# stepup-uc3845.net
KiCad netlist of a schematic drawn in EAGLE
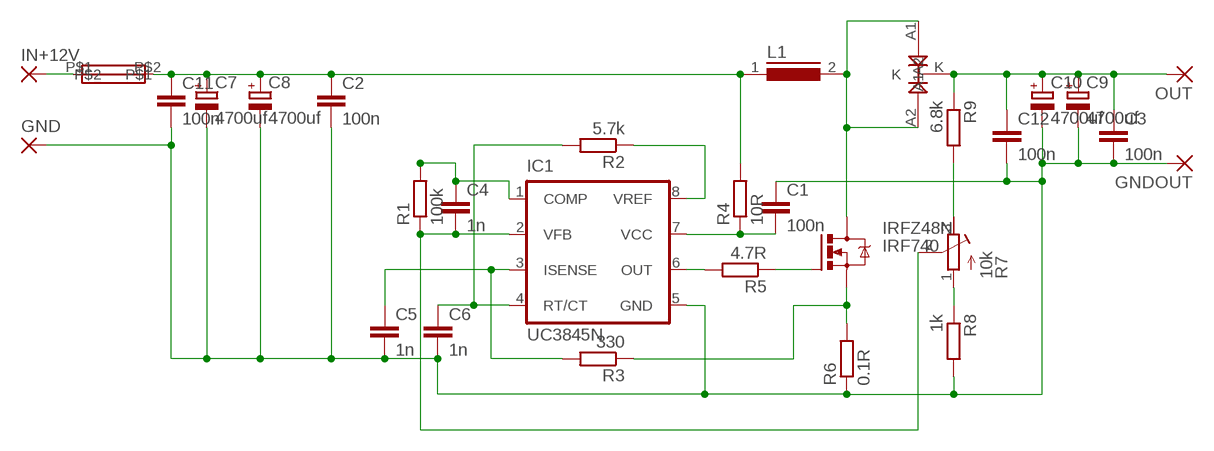
[diagram p0: schematic, sheet 1]

(export (version "E")
  (design (tool "Eeschema 10.0.6"))
  (components
    (comp (ref "C1")
      (value "100n")
      (footprint "eagle-import:C050-025X075")
      (libsource (lib "eagle-import") (part "C-EU050-025X075"))
    )
    (comp (ref "C2")
      (value "100n")
      (footprint "eagle-import:C050-025X075")
      (libsource (lib "eagle-import") (part "C-EU050-025X075"))
    )
    (comp (ref "C3")
      (value "100n")
      (footprint "eagle-import:C050-025X075")
      (libsource (lib "eagle-import") (part "C-EU050-025X075"))
    )
    (comp (ref "C4")
      (value "1n")
      (footprint "eagle-import:C050-025X075")
      (libsource (lib "eagle-import") (part "C-EU050-025X075"))
    )
    (comp (ref "C5")
      (value "1n")
      (footprint "eagle-import:C050-025X075")
      (libsource (lib "eagle-import") (part "C-EU050-025X075"))
    )
    (comp (ref "C6")
      (value "1n")
      (footprint "eagle-import:C050-025X075")
      (libsource (lib "eagle-import") (part "C-EU050-025X075"))
    )
    (comp (ref "C7")
      (value "4700uf")
      (footprint "eagle-import:E7,5-16")
      (libsource (lib "eagle-import") (part "CPOL-EUE7.5-16"))
    )
    (comp (ref "C8")
      (value "4700uf")
      (footprint "eagle-import:E7,5-16")
      (libsource (lib "eagle-import") (part "CPOL-EUE7.5-16"))
    )
    (comp (ref "C9")
      (value "4700uf")
      (footprint "eagle-import:E7,5-18")
      (libsource (lib "eagle-import") (part "CPOL-EUE7.5-18"))
    )
    (comp (ref "C10")
      (value "4700uf")
      (footprint "eagle-import:E7,5-18")
      (libsource (lib "eagle-import") (part "CPOL-EUE7.5-18"))
    )
    (comp (ref "C11")
      (value "100n")
      (footprint "eagle-import:C050-025X075")
      (libsource (lib "eagle-import") (part "C-EU050-025X075"))
    )
    (comp (ref "C12")
      (value "100n")
      (footprint "eagle-import:C050-025X075")
      (libsource (lib "eagle-import") (part "C-EU050-025X075"))
    )
    (comp (ref "F1")
      (value "10A")
      (footprint "eagle-import:FUSE38X12")
      (libsource (lib "eagle-import") (part "FUSE38X12"))
    )
    (comp (ref "GND")
      (value "3,81/1,1")
      (footprint "eagle-import:3,81_1,1")
      (libsource (lib "eagle-import") (part "3,81/1,1"))
    )
    (comp (ref "GNDOUT")
      (value "3,81/1,1")
      (footprint "eagle-import:3,81_1,1")
      (libsource (lib "eagle-import") (part "3,81/1,1"))
    )
    (comp (ref "IC1")
      (value "UC3845N")
      (footprint "eagle-import:DIL08")
      (libsource (lib "eagle-import") (part "UC384N5"))
    )
    (comp (ref "IN+12V")
      (value "3,81/1,1")
      (footprint "eagle-import:3,81_1,1")
      (libsource (lib "eagle-import") (part "3,81/1,1"))
    )
    (comp (ref "IRFZ48N")
      (value "IRF740")
      (footprint "eagle-import:TO220BV")
      (libsource (lib "eagle-import") (part "IRF740"))
    )
    (comp (ref "L1")
      (value "R3311D11")
      (footprint "eagle-import:11-33")
      (libsource (lib "eagle-import") (part "R3311D11"))
    )
    (comp (ref "OUT")
      (value "3,81/1,1")
      (footprint "eagle-import:3,81_1,1")
      (libsource (lib "eagle-import") (part "3,81/1,1"))
    )
    (comp (ref "R1")
      (value "100k")
      (footprint "eagle-import:0204_7")
      (libsource (lib "eagle-import") (part "resistor_348_R-EU_0204/7"))
    )
    (comp (ref "R2")
      (value "5.7k")
      (footprint "eagle-import:0207_7")
      (libsource (lib "eagle-import") (part "R-EU_0207/7"))
    )
    (comp (ref "R3")
      (value "330")
      (footprint "eagle-import:0207_7")
      (libsource (lib "eagle-import") (part "R-EU_0207/7"))
    )
    (comp (ref "R4")
      (value "10R")
      (footprint "eagle-import:0617_17")
      (libsource (lib "eagle-import") (part "resistor_348_R-EU_0617/17"))
    )
    (comp (ref "R5")
      (value "4.7R")
      (footprint "eagle-import:0207_7")
      (libsource (lib "eagle-import") (part "R-EU_0207/7"))
    )
    (comp (ref "R6")
      (value "0.1R")
      (footprint "eagle-import:0922_22")
      (libsource (lib "eagle-import") (part "resistor_348_R-EU_0922/22"))
    )
    (comp (ref "R7")
      (value "10k")
      (footprint "eagle-import:RTRIM3296W")
      (libsource (lib "eagle-import") (part "R-TRIMM3296W"))
    )
    (comp (ref "R8")
      (value "1k")
      (footprint "eagle-import:0207_7")
      (libsource (lib "eagle-import") (part "R-EU_0207/7"))
    )
    (comp (ref "R9")
      (value "6.8k")
      (footprint "eagle-import:0207_7")
      (libsource (lib "eagle-import") (part "R-EU_0207/7"))
    )
    (comp (ref "U$1")
      (value "TO-247-SHOTTKY-K")
      (footprint "eagle-import:TO-247")
      (libsource (lib "eagle-import") (part "TO-247-SHOTTKY-K"))
    )
  )
  (nets
    (net (code "1") (name "Net-(C11-Pad1)") (class "Default")
      (node (ref "C11") (pin "1") (pinfunction "1_1") (pintype "passive"))
      (node (ref "C2") (pin "1") (pinfunction "1_1") (pintype "passive"))
      (node (ref "C7") (pin "+") (pinfunction "+_+") (pintype "passive"))
      (node (ref "C8") (pin "+") (pinfunction "+_+") (pintype "passive"))
      (node (ref "F1") (pin "P$2") (pinfunction "P$2_P$2") (pintype "bidirectional"))
      (node (ref "L1") (pin "1") (pinfunction "1_1") (pintype "passive"))
      (node (ref "R4") (pin "2") (pinfunction "2_2") (pintype "passive"))
    )
    (net (code "2") (name "Net-(GND-P)") (class "Default")
      (node (ref "C1") (pin "1") (pinfunction "1_1") (pintype "passive"))
      (node (ref "C10") (pin "-") (pinfunction "-_-") (pintype "passive"))
      (node (ref "C11") (pin "2") (pinfunction "2_2") (pintype "passive"))
      (node (ref "C12") (pin "2") (pinfunction "2_2") (pintype "passive"))
      (node (ref "C2") (pin "2") (pinfunction "2_2") (pintype "passive"))
      (node (ref "C3") (pin "2") (pinfunction "2_2") (pintype "passive"))
      (node (ref "C5") (pin "2") (pinfunction "2_2") (pintype "passive"))
      (node (ref "C6") (pin "2") (pinfunction "2_2") (pintype "passive"))
      (node (ref "C7") (pin "-") (pinfunction "-_-") (pintype "passive"))
      (node (ref "C8") (pin "-") (pinfunction "-_-") (pintype "passive"))
      (node (ref "C9") (pin "-") (pinfunction "-_-") (pintype "passive"))
      (node (ref "GND") (pin "1") (pinfunction "P_1") (pintype "passive"))
      (node (ref "GNDOUT") (pin "1") (pinfunction "P_1") (pintype "passive"))
      (node (ref "IC1") (pin "5") (pinfunction "GND_5") (pintype "power_in"))
      (node (ref "R6") (pin "1") (pinfunction "1_1") (pintype "passive"))
      (node (ref "R8") (pin "2") (pinfunction "2_2") (pintype "passive"))
    )
    (net (code "3") (name "Net-(IC1-COMP)") (class "Default")
      (node (ref "C4") (pin "1") (pinfunction "1_1") (pintype "passive"))
      (node (ref "IC1") (pin "1") (pinfunction "COMP_1") (pintype "passive"))
      (node (ref "R1") (pin "2") (pinfunction "2_2") (pintype "passive"))
    )
    (net (code "4") (name "Net-(IC1-ISENSE)") (class "Default")
      (node (ref "C5") (pin "1") (pinfunction "1_1") (pintype "passive"))
      (node (ref "IC1") (pin "3") (pinfunction "ISENSE_3") (pintype "input"))
      (node (ref "R3") (pin "2") (pinfunction "2_2") (pintype "passive"))
    )
    (net (code "5") (name "Net-(IC1-OUT)") (class "Default")
      (node (ref "IC1") (pin "6") (pinfunction "OUT_6") (pintype "output"))
      (node (ref "R5") (pin "2") (pinfunction "2_2") (pintype "passive"))
    )
    (net (code "6") (name "Net-(IC1-RT{slash}CT)") (class "Default")
      (node (ref "C6") (pin "1") (pinfunction "1_1") (pintype "passive"))
      (node (ref "IC1") (pin "4") (pinfunction "RT/CT_4") (pintype "passive"))
      (node (ref "R2") (pin "2") (pinfunction "2_2") (pintype "passive"))
    )
    (net (code "7") (name "Net-(IC1-VCC)") (class "Default")
      (node (ref "C1") (pin "2") (pinfunction "2_2") (pintype "passive"))
      (node (ref "IC1") (pin "7") (pinfunction "VCC_7") (pintype "power_in"))
      (node (ref "R4") (pin "1") (pinfunction "1_1") (pintype "passive"))
    )
    (net (code "8") (name "Net-(IC1-VFB)") (class "Default")
      (node (ref "C4") (pin "2") (pinfunction "2_2") (pintype "passive"))
      (node (ref "IC1") (pin "2") (pinfunction "VFB_2") (pintype "input"))
      (node (ref "R1") (pin "1") (pinfunction "1_1") (pintype "passive"))
      (node (ref "R7") (pin "2") (pinfunction "S_2") (pintype "passive"))
    )
    (net (code "9") (name "Net-(IC1-VREF)") (class "Default")
      (node (ref "IC1") (pin "8") (pinfunction "VREF_8") (pintype "passive"))
      (node (ref "R2") (pin "1") (pinfunction "1_1") (pintype "passive"))
    )
    (net (code "10") (name "Net-(IN+12V-P)") (class "Default")
      (node (ref "F1") (pin "P$1") (pinfunction "P$1_P$1") (pintype "bidirectional"))
      (node (ref "IN+12V") (pin "1") (pinfunction "P_1") (pintype "passive"))
    )
    (net (code "11") (name "Net-(IRFZ48N-PadD)") (class "Default")
      (node (ref "IRFZ48N") (pin "D") (pinfunction "D_D") (pintype "passive"))
      (node (ref "L1") (pin "2") (pinfunction "2_2") (pintype "passive"))
      (node (ref "U$1") (pin "A1") (pinfunction "A1_A1") (pintype "bidirectional"))
      (node (ref "U$1") (pin "A2") (pinfunction "A2_A2") (pintype "bidirectional"))
    )
    (net (code "12") (name "Net-(IRFZ48N-PadG)") (class "Default")
      (node (ref "IRFZ48N") (pin "G") (pinfunction "G_G") (pintype "passive"))
      (node (ref "R5") (pin "1") (pinfunction "1_1") (pintype "passive"))
    )
    (net (code "13") (name "Net-(IRFZ48N-PadS)") (class "Default")
      (node (ref "IRFZ48N") (pin "S") (pinfunction "S_S") (pintype "passive"))
      (node (ref "R3") (pin "1") (pinfunction "1_1") (pintype "passive"))
      (node (ref "R6") (pin "2") (pinfunction "2_2") (pintype "passive"))
    )
    (net (code "14") (name "Net-(OUT-P)") (class "Default")
      (node (ref "C10") (pin "+") (pinfunction "+_+") (pintype "passive"))
      (node (ref "C12") (pin "1") (pinfunction "1_1") (pintype "passive"))
      (node (ref "C3") (pin "1") (pinfunction "1_1") (pintype "passive"))
      (node (ref "C9") (pin "+") (pinfunction "+_+") (pintype "passive"))
      (node (ref "OUT") (pin "1") (pinfunction "P_1") (pintype "passive"))
      (node (ref "R9") (pin "1") (pinfunction "1_1") (pintype "passive"))
      (node (ref "U$1") (pin "K") (pinfunction "K_K") (pintype "bidirectional"))
    )
    (net (code "15") (name "Net-(R7-A)") (class "Default")
      (node (ref "R7") (pin "1") (pinfunction "A_1") (pintype "passive"))
      (node (ref "R8") (pin "1") (pinfunction "1_1") (pintype "passive"))
    )
    (net (code "16") (name "Net-(R7-E)") (class "Default")
      (node (ref "R7") (pin "3") (pinfunction "E_3") (pintype "passive"))
      (node (ref "R9") (pin "2") (pinfunction "2_2") (pintype "passive"))
    )
  )
)
